# QPA9120.net
KiCad netlist of a schematic drawn in Altium Designer
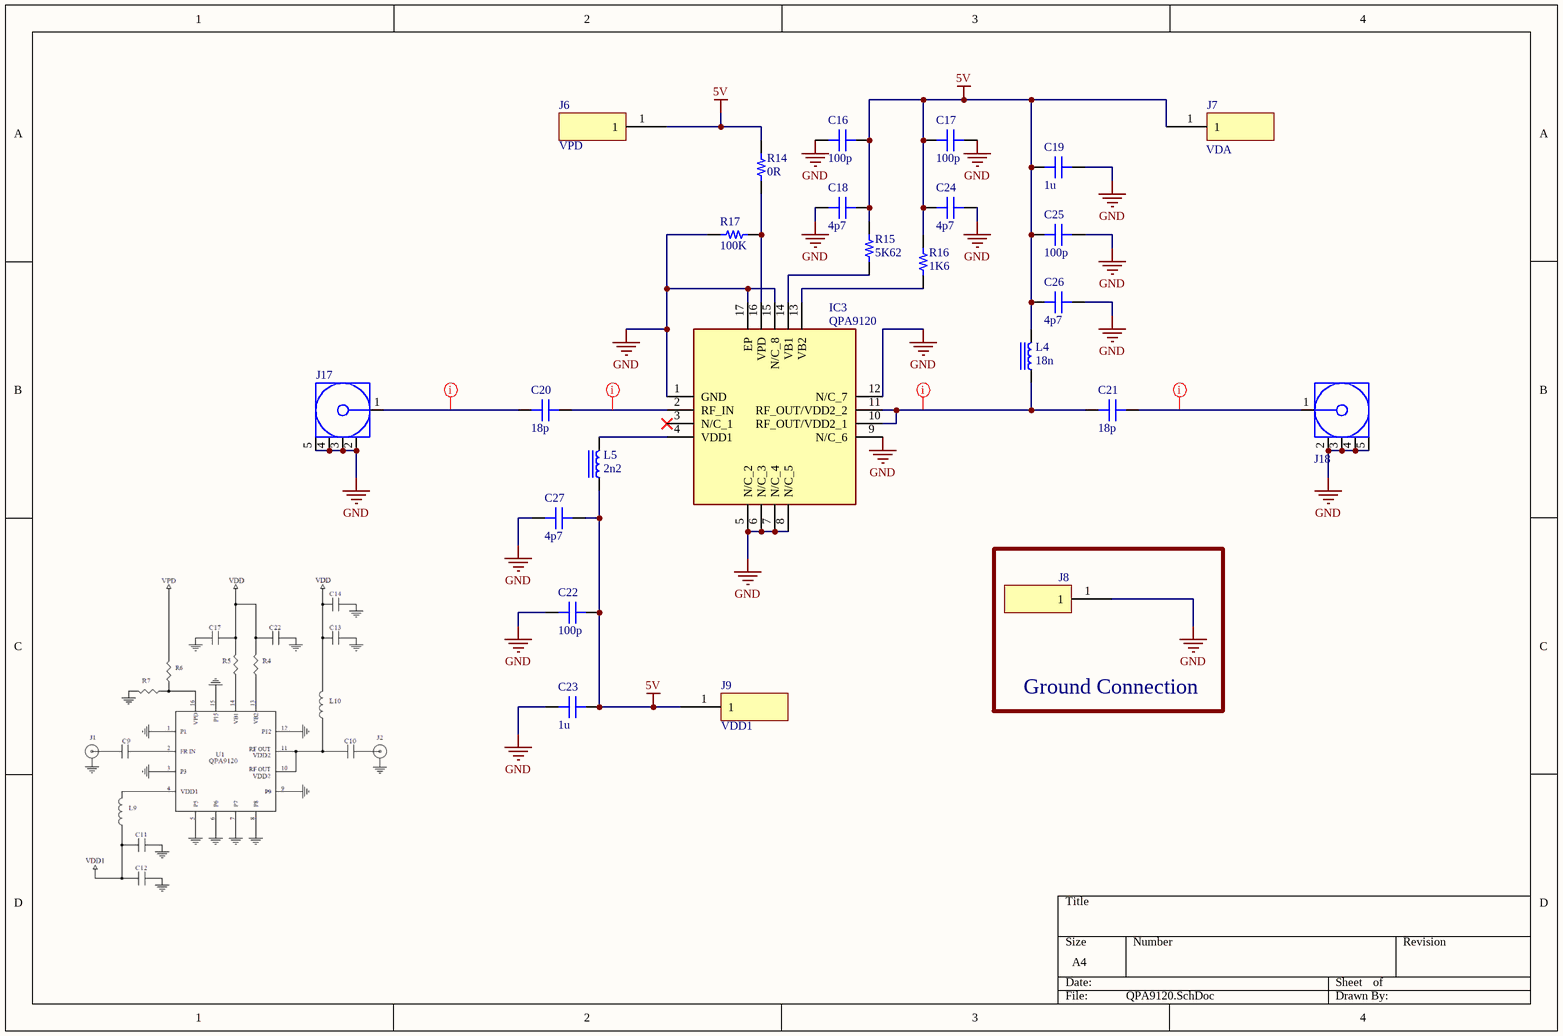
[diagram p0: QPA9120.SchDoc]

(export (version "E")
  (design (tool "Eeschema 10.0.6"))
  (components
    (comp (ref "C16")
      (value "100p")
      (footprint "CAP 0603_1608 RF")
      (description "CAP CER 100PF 250V NP0 0603")
      (fields
        (field (name "PART NUMBER") "600S101GW250XT")
        (field (name "MANUFACTURER") "American Technical Ceramics")
      )
      (libsource (lib "Celestial Altium Library - altium_library") (part "Capacitor"))
    )
    (comp (ref "C17")
      (value "100p")
      (footprint "CAP 0603_1608 RF")
      (description "CAP CER 100PF 250V NP0 0603")
      (fields
        (field (name "PART NUMBER") "600S101GW250XT")
        (field (name "MANUFACTURER") "American Technical Ceramics")
      )
      (libsource (lib "Celestial Altium Library - altium_library") (part "Capacitor"))
    )
    (comp (ref "C18")
      (value "4p7")
      (footprint "CAP 0402_1005 RF")
      (description "CAP CER 4.7PF 200V C0G/NP0 0402")
      (fields
        (field (name "PART NUMBER") "600L4R7BT200T")
        (field (name "MANUFACTURER") "American Technical Ceramics")
      )
      (libsource (lib "Celestial Altium Library - altium_library") (part "Capacitor"))
    )
    (comp (ref "C19")
      (value "1u")
      (footprint "CAP 0603_1608")
      (description "CAP CER 1UF 25V X7R 0603")
      (fields
        (field (name "PART NUMBER") "GCM188R71E105KA64J")
        (field (name "MANUFACTURER") "Murata Electronics")
      )
      (libsource (lib "Celestial Altium Library - altium_library") (part "Capacitor"))
    )
    (comp (ref "C20")
      (value "18p")
      (footprint "CAP 0402_1005 RF")
      (description "CAP CER 18PF 200V NP0 0402")
      (fields
        (field (name "PART NUMBER") "600L180GT200T")
        (field (name "MANUFACTURER") "American Technical Ceramics")
      )
      (libsource (lib "Celestial Altium Library - altium_library") (part "Capacitor"))
    )
    (comp (ref "C21")
      (value "18p")
      (footprint "CAP 0402_1005 RF")
      (description "CAP CER 18PF 200V NP0 0402")
      (fields
        (field (name "PART NUMBER") "600L180GT200T")
        (field (name "MANUFACTURER") "American Technical Ceramics")
      )
      (libsource (lib "Celestial Altium Library - altium_library") (part "Capacitor"))
    )
    (comp (ref "C22")
      (value "100p")
      (footprint "CAP 0603_1608 RF")
      (description "CAP CER 100PF 250V NP0 0603")
      (fields
        (field (name "PART NUMBER") "600S101GW250XT")
        (field (name "MANUFACTURER") "American Technical Ceramics")
      )
      (libsource (lib "Celestial Altium Library - altium_library") (part "Capacitor"))
    )
    (comp (ref "C23")
      (value "1u")
      (footprint "CAP 0603_1608")
      (description "CAP CER 1UF 25V X7R 0603")
      (fields
        (field (name "PART NUMBER") "GCM188R71E105KA64J")
        (field (name "MANUFACTURER") "Murata Electronics")
      )
      (libsource (lib "Celestial Altium Library - altium_library") (part "Capacitor"))
    )
    (comp (ref "C24")
      (value "4p7")
      (footprint "CAP 0402_1005 RF")
      (description "CAP CER 4.7PF 200V C0G/NP0 0402")
      (fields
        (field (name "PART NUMBER") "600L4R7BT200T")
        (field (name "MANUFACTURER") "American Technical Ceramics")
      )
      (libsource (lib "Celestial Altium Library - altium_library") (part "Capacitor"))
    )
    (comp (ref "C25")
      (value "100p")
      (footprint "CAP 0603_1608 RF")
      (description "CAP CER 100PF 250V NP0 0603")
      (fields
        (field (name "PART NUMBER") "600S101GW250XT")
        (field (name "MANUFACTURER") "American Technical Ceramics")
      )
      (libsource (lib "Celestial Altium Library - altium_library") (part "Capacitor"))
    )
    (comp (ref "C26")
      (value "4p7")
      (footprint "CAP 0402_1005 RF")
      (description "CAP CER 4.7PF 200V C0G/NP0 0402")
      (fields
        (field (name "PART NUMBER") "600L4R7BT200T")
        (field (name "MANUFACTURER") "American Technical Ceramics")
      )
      (libsource (lib "Celestial Altium Library - altium_library") (part "Capacitor"))
    )
    (comp (ref "C27")
      (value "4p7")
      (footprint "CAP 0402_1005 RF")
      (description "CAP CER 4.7PF 200V C0G/NP0 0402")
      (fields
        (field (name "PART NUMBER") "600L4R7BT200T")
        (field (name "MANUFACTURER") "American Technical Ceramics")
      )
      (libsource (lib "Celestial Altium Library - altium_library") (part "Capacitor"))
    )
    (comp (ref "IC3")
      (value "QPA9120")
      (footprint "SamacSys:QFN50P300X300X86-17N-D")
      (description "Integrated Circuit")
      (libsource (lib "SamacSys") (part "QPA9120"))
    )
    (comp (ref "J6")
      (value "Nail_Head")
      (footprint "Nail_Head")
      (description "1460-2-00-80-00-00-03-0 Mill-Max")
      (libsource (lib "") (part "Nail_Head_1"))
    )
    (comp (ref "J7")
      (value "Nail_Head")
      (footprint "Nail_Head")
      (description "1460-2-00-80-00-00-03-0 Mill-Max")
      (libsource (lib "ARIS_COM_Transponder") (part "Nail_Head"))
    )
    (comp (ref "J8")
      (value "Nail_Head")
      (footprint "Nail_Head")
      (description "1460-2-00-80-00-00-03-0 Mill-Max")
      (libsource (lib "") (part "Nail_Head_1"))
    )
    (comp (ref "J9")
      (value "Nail_Head")
      (footprint "Nail_Head")
      (description "1460-2-00-80-00-00-03-0 Mill-Max")
      (libsource (lib "ARIS_COM_Transponder") (part "Nail_Head"))
    )
    (comp (ref "J17")
      (value "60312202114513")
      (footprint "60312202114513")
      (description "WR-SMA Connector, PCB End Launch Jack, 6.35SQ Flange Flat Tab 1.6mm, DC~18GHz, 50Ohm")
      (fields (field (name "MANUFACTURER") "Wurth Elektronik"))
      (libsource (lib "Altium_WR-SMA (rev23a)") (part "60312202114513"))
    )
    (comp (ref "J18")
      (value "60312202114513")
      (footprint "60312202114513")
      (description "WR-SMA Connector, PCB End Launch Jack, 6.35SQ Flange Flat Tab 1.6mm, DC~18GHz, 50Ohm")
      (fields (field (name "MANUFACTURER") "Wurth Elektronik"))
      (libsource (lib "Altium_WR-SMA (rev23a)") (part "60312202114513"))
    )
    (comp (ref "L4")
      (value "18n")
      (footprint "IND 0402_1005 RF WW")
      (description "FIXED IND 18NH 1.05A 0.13OHM SMD")
      (fields
        (field (name "PART NUMBER") "LQW15AN18NG8ZD")
        (field (name "MANUFACTURER") "Murata Electronics")
      )
      (libsource (lib "Celestial Altium Library - altium_library") (part "Inductor"))
    )
    (comp (ref "L5")
      (value "2n2")
      (footprint "IND 0402_1005 RF WW")
      (description "FIXED IND 2.2NH 2.53A 0.022OHM")
      (fields
        (field (name "PART NUMBER") "LQW15AN2N2D8ZD")
        (field (name "MANUFACTURER") "Murata Electronics")
      )
      (libsource (lib "Celestial Altium Library - altium_library") (part "Inductor"))
    )
    (comp (ref "R14")
      (value "0R")
      (footprint "RES 0603_1608")
      (description "0603 26 AMP JUMPER")
      (fields (field (name "PART NUMBER") "JR0603X26E") (field (name "MANUFACTURER") "Ohmite"))
      (libsource (lib "Celestial Altium Library - altium_library") (part "Resistor"))
    )
    (comp (ref "R15")
      (value "5K62")
      (footprint "RES 0402_1005")
      (description "RES SMD 5.62K OHM 1% 1/16W 0402")
      (fields (field (name "PART NUMBER") "CRCW04025K62FKED") (field (name "MANUFACTURER") "Vishay Dale"))
      (libsource (lib "Celestial Altium Library - altium_library") (part "Resistor"))
    )
    (comp (ref "R16")
      (value "1K6")
      (footprint "RES 0402_1005")
      (description "RES SMD 1.6K OHM 1% 1/16W 0402")
      (fields (field (name "PART NUMBER") "CR0402-FX-1601GLF") (field (name "MANUFACTURER") "Bourns Inc."))
      (libsource (lib "Celestial Altium Library - altium_library") (part "Resistor"))
    )
    (comp (ref "R17")
      (value "100K")
      (footprint "RES 0402_1005")
      (description "RES SMD 100K OHM 1% 1/5W 0402")
      (fields (field (name "PART NUMBER") "CRCW0402100KFKEDHP") (field (name "MANUFACTURER") "Vishay Dale"))
      (libsource (lib "Celestial Altium Library - altium_library") (part "Resistor"))
    )
  )
  (nets
    (net (code "1") (name "5V") (class "Default")
      (node (ref "C16") (pin "2") (pinfunction "2_2") (pintype "passive"))
      (node (ref "C17") (pin "1") (pinfunction "1_1") (pintype "passive"))
      (node (ref "C18") (pin "2") (pinfunction "2_2") (pintype "passive"))
      (node (ref "C19") (pin "1") (pinfunction "1_1") (pintype "passive"))
      (node (ref "C22") (pin "2") (pinfunction "2_2") (pintype "passive"))
      (node (ref "C23") (pin "2") (pinfunction "2_2") (pintype "passive"))
      (node (ref "C24") (pin "1") (pinfunction "1_1") (pintype "passive"))
      (node (ref "C25") (pin "1") (pinfunction "1_1") (pintype "passive"))
      (node (ref "C26") (pin "1") (pinfunction "1_1") (pintype "passive"))
      (node (ref "C27") (pin "2") (pinfunction "2_2") (pintype "passive"))
      (node (ref "J6") (pin "1") (pinfunction "1_1") (pintype "passive"))
      (node (ref "J7") (pin "1") (pinfunction "1_1") (pintype "passive"))
      (node (ref "J9") (pin "1") (pinfunction "1_1") (pintype "passive"))
      (node (ref "L4") (pin "2") (pinfunction "2_2") (pintype "passive"))
      (node (ref "L5") (pin "1") (pinfunction "1_1") (pintype "passive"))
      (node (ref "R14") (pin "2") (pinfunction "2_2") (pintype "passive"))
      (node (ref "R15") (pin "2") (pinfunction "2_2") (pintype "passive"))
      (node (ref "R16") (pin "2") (pinfunction "2_2") (pintype "passive"))
    )
    (net (code "2") (name "GND") (class "Default")
      (node (ref "C16") (pin "1") (pinfunction "1_1") (pintype "passive"))
      (node (ref "C17") (pin "2") (pinfunction "2_2") (pintype "passive"))
      (node (ref "C18") (pin "1") (pinfunction "1_1") (pintype "passive"))
      (node (ref "C19") (pin "2") (pinfunction "2_2") (pintype "passive"))
      (node (ref "C22") (pin "1") (pinfunction "1_1") (pintype "passive"))
      (node (ref "C23") (pin "1") (pinfunction "1_1") (pintype "passive"))
      (node (ref "C24") (pin "2") (pinfunction "2_2") (pintype "passive"))
      (node (ref "C25") (pin "2") (pinfunction "2_2") (pintype "passive"))
      (node (ref "C26") (pin "2") (pinfunction "2_2") (pintype "passive"))
      (node (ref "C27") (pin "1") (pinfunction "1_1") (pintype "passive"))
      (node (ref "IC3") (pin "1") (pinfunction "GND_1") (pintype "passive"))
      (node (ref "IC3") (pin "12") (pinfunction "N/C_7_12") (pintype "passive"))
      (node (ref "IC3") (pin "15") (pinfunction "N/C_8_15") (pintype "passive"))
      (node (ref "IC3") (pin "17") (pinfunction "EP_17") (pintype "passive"))
      (node (ref "IC3") (pin "5") (pinfunction "N/C_2_5") (pintype "passive"))
      (node (ref "IC3") (pin "6") (pinfunction "N/C_3_6") (pintype "passive"))
      (node (ref "IC3") (pin "7") (pinfunction "N/C_4_7") (pintype "passive"))
      (node (ref "IC3") (pin "8") (pinfunction "N/C_5_8") (pintype "passive"))
      (node (ref "IC3") (pin "9") (pinfunction "N/C_6_9") (pintype "passive"))
      (node (ref "J17") (pin "2") (pinfunction "GND_2") (pintype "passive"))
      (node (ref "J17") (pin "3") (pinfunction "GND_3") (pintype "passive"))
      (node (ref "J17") (pin "4") (pinfunction "GND_4") (pintype "passive"))
      (node (ref "J17") (pin "5") (pinfunction "GND_5") (pintype "passive"))
      (node (ref "J18") (pin "2") (pinfunction "GND_2") (pintype "passive"))
      (node (ref "J18") (pin "3") (pinfunction "GND_3") (pintype "passive"))
      (node (ref "J18") (pin "4") (pinfunction "GND_4") (pintype "passive"))
      (node (ref "J18") (pin "5") (pinfunction "GND_5") (pintype "passive"))
      (node (ref "J8") (pin "1") (pinfunction "1_1") (pintype "passive"))
      (node (ref "R17") (pin "1") (pinfunction "1_1") (pintype "passive"))
    )
    (net (code "3") (name "Net-(IC3-RF_IN)") (class "Default")
      (node (ref "C20") (pin "2") (pinfunction "2_2") (pintype "passive"))
      (node (ref "IC3") (pin "2") (pinfunction "RF_IN_2") (pintype "passive"))
    )
    (net (code "4") (name "Net-(IC3-RF_OUT{slash}VDD2_1)") (class "Default")
      (node (ref "C21") (pin "1") (pinfunction "1_1") (pintype "passive"))
      (node (ref "IC3") (pin "10") (pinfunction "RF_OUT/VDD2_1_10") (pintype "passive"))
      (node (ref "IC3") (pin "11") (pinfunction "RF_OUT/VDD2_2_11") (pintype "passive"))
      (node (ref "L4") (pin "1") (pinfunction "1_1") (pintype "passive"))
    )
    (net (code "5") (name "Net-(IC3-VB1)") (class "Default")
      (node (ref "IC3") (pin "14") (pinfunction "VB1_14") (pintype "passive"))
      (node (ref "R15") (pin "1") (pinfunction "1_1") (pintype "passive"))
    )
    (net (code "6") (name "Net-(IC3-VB2)") (class "Default")
      (node (ref "IC3") (pin "13") (pinfunction "VB2_13") (pintype "passive"))
      (node (ref "R16") (pin "1") (pinfunction "1_1") (pintype "passive"))
    )
    (net (code "7") (name "Net-(IC3-VDD1)") (class "Default")
      (node (ref "IC3") (pin "4") (pinfunction "VDD1_4") (pintype "passive"))
      (node (ref "L5") (pin "2") (pinfunction "2_2") (pintype "passive"))
    )
    (net (code "8") (name "Net-(IC3-VPD)") (class "Default")
      (node (ref "IC3") (pin "16") (pinfunction "VPD_16") (pintype "passive"))
      (node (ref "R14") (pin "1") (pinfunction "1_1") (pintype "passive"))
      (node (ref "R17") (pin "2") (pinfunction "2_2") (pintype "passive"))
    )
    (net (code "9") (name "Net-(J17-Signal)") (class "Default")
      (node (ref "C20") (pin "1") (pinfunction "1_1") (pintype "passive"))
      (node (ref "J17") (pin "1") (pinfunction "Signal_1") (pintype "passive"))
    )
    (net (code "10") (name "Net-(J18-Signal)") (class "Default")
      (node (ref "C21") (pin "2") (pinfunction "2_2") (pintype "passive"))
      (node (ref "J18") (pin "1") (pinfunction "Signal_1") (pintype "passive"))
    )
    (net (code "11") (name "unconnected-(IC3-N{slash}C_1-Pad3)") (class "Default")
      (node (ref "IC3") (pin "3") (pinfunction "N/C_1_3") (pintype "passive+no_connect"))
    )
  )
)
